# DM1095_LEFT_OV7251.net
KiCad netlist of a schematic drawn in Altium Designer
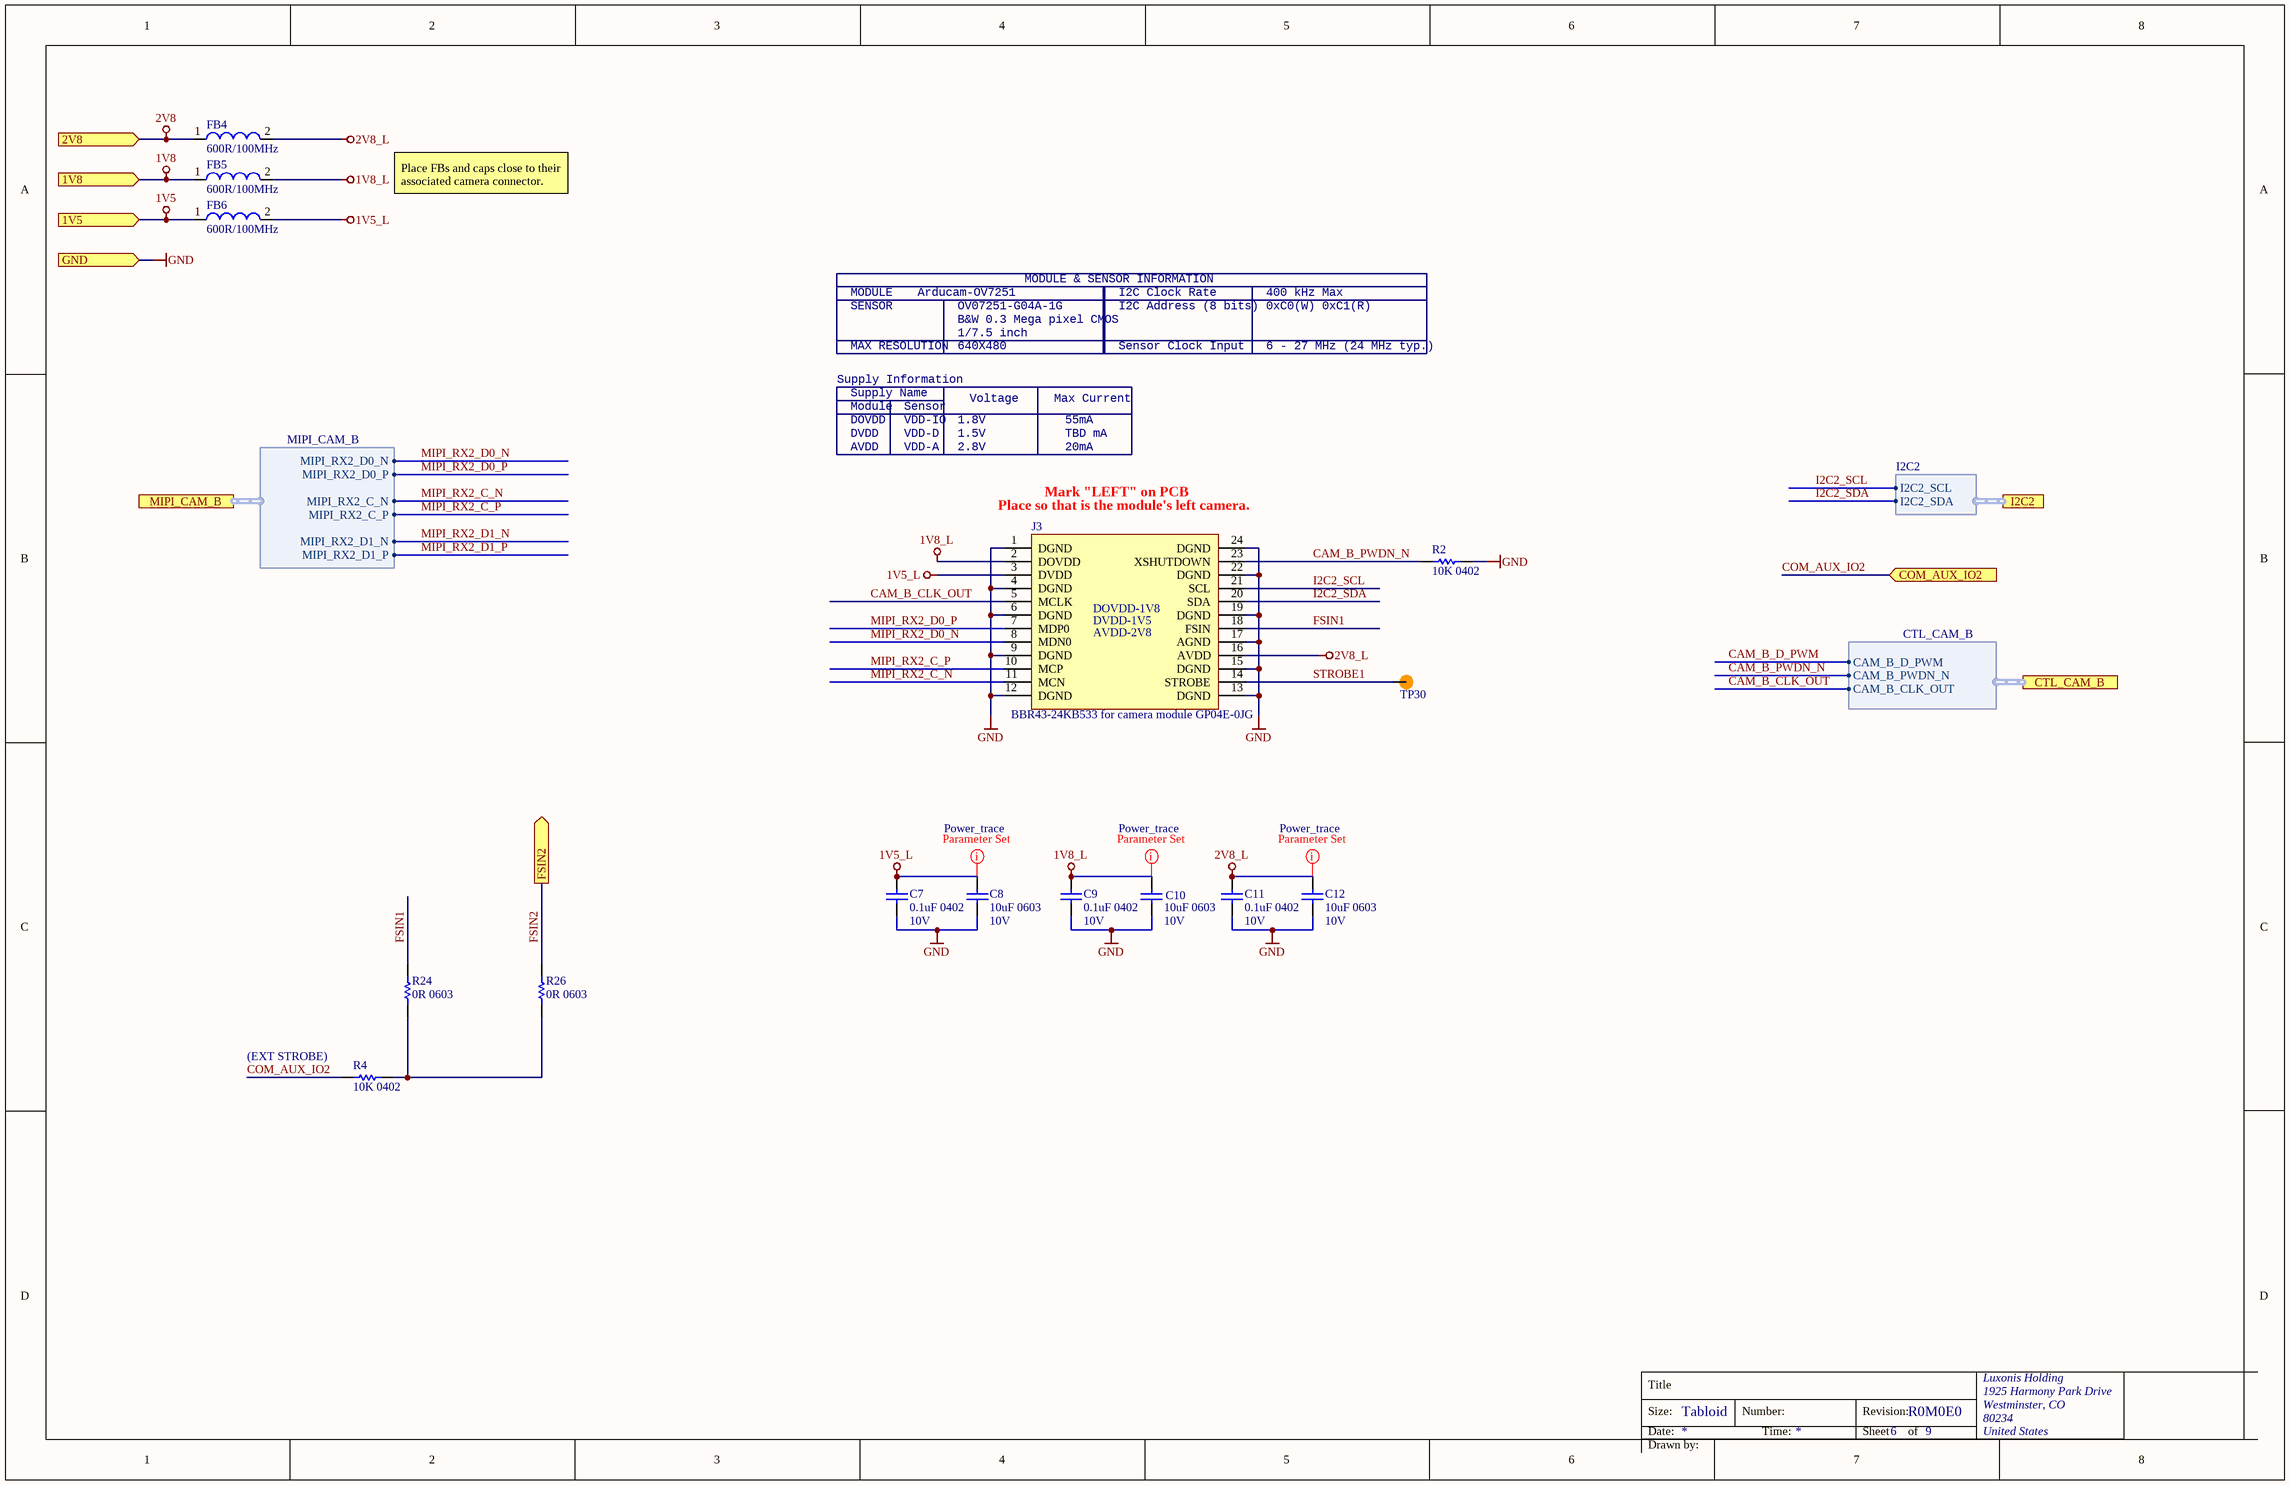
[diagram p0: DM1095_LEFT_OV7251.SchDoc]

(export (version "E")
  (design (tool "Eeschema 10.0.6"))
  (components
    (comp (ref "C7")
      (value "0.1uF 0402")
      (footprint "CAP_Altium_Vault_Generic:CAPC0402(1005)70_L")
      (description "CAP CER 0.1UF 10V X7R 0402 5%")
      (fields (field (name "TOLERANCE") "5%") (field (name "VOLTAGE RATING") "10V"))
      (libsource (lib "LuxonisMaster") (part "GRM155R71A104JA01D"))
    )
    (comp (ref "C8")
      (value "10uF 0603")
      (footprint "CAP_Altium_Vault_Generic:CAPC0603(1608)100_L")
      (description "CAP CER 10UF 10V X5R 0603 20%")
      (fields (field (name "TOLERANCE") "20%") (field (name "VOLTAGE RATING") "10V"))
      (libsource (lib "LuxonisMaster") (part "GRM188R61A106ME69D"))
    )
    (comp (ref "C9")
      (value "0.1uF 0402")
      (footprint "CAP_Altium_Vault_Generic:CAPC0402(1005)70_L")
      (description "CAP CER 0.1UF 10V X7R 0402 5%")
      (fields (field (name "TOLERANCE") "5%") (field (name "VOLTAGE RATING") "10V"))
      (libsource (lib "LuxonisMaster") (part "GRM155R71A104JA01D"))
    )
    (comp (ref "C10")
      (value "10uF 0603")
      (footprint "CAP_Altium_Vault_Generic:CAPC0603(1608)100_L")
      (description "CAP CER 10UF 10V X5R 0603 20%")
      (fields (field (name "TOLERANCE") "20%") (field (name "VOLTAGE RATING") "10V"))
      (libsource (lib "LuxonisMaster") (part "GRM188R61A106ME69D"))
    )
    (comp (ref "C11")
      (value "0.1uF 0402")
      (footprint "CAP_Altium_Vault_Generic:CAPC0402(1005)70_L")
      (description "CAP CER 0.1UF 10V X7R 0402 5%")
      (fields (field (name "TOLERANCE") "5%") (field (name "VOLTAGE RATING") "10V"))
      (libsource (lib "LuxonisMaster") (part "GRM155R71A104JA01D"))
    )
    (comp (ref "C12")
      (value "10uF 0603")
      (footprint "CAP_Altium_Vault_Generic:CAPC0603(1608)100_L")
      (description "CAP CER 10UF 10V X5R 0603 20%")
      (fields (field (name "TOLERANCE") "20%") (field (name "VOLTAGE RATING") "10V"))
      (libsource (lib "LuxonisMaster") (part "GRM188R61A106ME69D"))
    )
    (comp (ref "FB4")
      (value "600R/100MHz")
      (footprint "LuxonisMaster:2508056017Y2")
      (description "FERRITE BEAD, 0.1OHM, 2A, 0805, 600R/100MHz")
      (fields (field (name "TOLERANCE") "25%"))
      (libsource (lib "LuxonisMaster") (part "2508056017Y2"))
    )
    (comp (ref "FB5")
      (value "600R/100MHz")
      (footprint "LuxonisMaster:2508056017Y2")
      (description "FERRITE BEAD, 0.1OHM, 2A, 0805, 600R/100MHz")
      (fields (field (name "TOLERANCE") "25%"))
      (libsource (lib "LuxonisMaster") (part "2508056017Y2"))
    )
    (comp (ref "FB6")
      (value "600R/100MHz")
      (footprint "LuxonisMaster:2508056017Y2")
      (description "FERRITE BEAD, 0.1OHM, 2A, 0805, 600R/100MHz")
      (fields (field (name "TOLERANCE") "25%"))
      (libsource (lib "LuxonisMaster") (part "2508056017Y2"))
    )
    (comp (ref "J3")
      (value "BBR43-24KB533 for camera module GP04E-0JG")
      (footprint "GP04E-0JG OV7251")
      (description "CONN 24 way, 2 row board to board connector SMD")
      (libsource (lib "DM1095") (part "GP04E-0JG_Connector"))
    )
    (comp (ref "R2")
      (value "10K 0402")
      (footprint "RES_Altium_Vault_Generic:RESC0402(1005)_L")
      (fields (field (name "TOLERANCE") "1%"))
      (libsource (lib "LuxonisMaster") (part "RC0402FR-1310KL"))
    )
    (comp (ref "R4")
      (value "10K 0402")
      (footprint "RES_Altium_Vault_Generic:RESC0402(1005)_L")
      (fields (field (name "TOLERANCE") "1%"))
      (libsource (lib "LuxonisMaster") (part "RC0402FR-1310KL"))
    )
    (comp (ref "R24")
      (value "0R 0603")
      (footprint "RES_Altium_Vault_Generic:RESC0603(1608)_N")
      (fields (field (name "TOLERANCE") "5%"))
      (libsource (lib "LuxonisMaster") (part "CRCW06030000Z0EA"))
    )
    (comp (ref "R26")
      (value "0R 0603")
      (footprint "RES_Altium_Vault_Generic:RESC0603(1608)_N")
      (fields (field (name "TOLERANCE") "5%"))
      (libsource (lib "LuxonisMaster") (part "CRCW06030000Z0EA"))
    )
    (comp (ref "TP30")
      (value "TP100_200_NS")
      (footprint "LuxonisMaster:TP100_200_NS")
      (libsource (lib "LuxonisMaster") (part "TEST_POINT"))
    )
  )
  (nets
    (net (code "4") (name "/CAM_B_CLK_OUT") (class "Default")
      (node (ref "J3") (pin "5") (pinfunction "MCLK_5") (pintype "passive"))
    )
    (net (code "6") (name "/CAM_B_PWDN_N") (class "Default")
      (node (ref "J3") (pin "23") (pinfunction "XSHUTDOWN_23") (pintype "passive"))
      (node (ref "R2") (pin "1") (pinfunction "1_1") (pintype "passive"))
    )
    (net (code "7") (name "/COM_AUX_IO2") (class "Default")
      (node (ref "R4") (pin "1") (pinfunction "1_1") (pintype "passive"))
    )
    (net (code "8") (name "/FSIN1") (class "Default")
      (node (ref "J3") (pin "18") (pinfunction "FSIN_18") (pintype "passive"))
      (node (ref "R24") (pin "2") (pinfunction "2_2") (pintype "passive"))
    )
    (net (code "9") (name "/FSIN2") (class "Default")
      (node (ref "R26") (pin "2") (pinfunction "2_2") (pintype "passive"))
    )
    (net (code "10") (name "/I2C2_SCL") (class "Default")
      (node (ref "J3") (pin "21") (pinfunction "SCL_21") (pintype "passive"))
    )
    (net (code "11") (name "/I2C2_SDA") (class "Default")
      (node (ref "J3") (pin "20") (pinfunction "SDA_20") (pintype "passive"))
    )
    (net (code "12") (name "/MIPI_RX2_C_N") (class "Default")
      (node (ref "J3") (pin "11") (pinfunction "MCN_11") (pintype "passive"))
    )
    (net (code "13") (name "/MIPI_RX2_C_P") (class "Default")
      (node (ref "J3") (pin "10") (pinfunction "MCP_10") (pintype "passive"))
    )
    (net (code "14") (name "/MIPI_RX2_D0_N") (class "Default")
      (node (ref "J3") (pin "8") (pinfunction "MDN0_8") (pintype "passive"))
    )
    (net (code "15") (name "/MIPI_RX2_D0_P") (class "Default")
      (node (ref "J3") (pin "7") (pinfunction "MDP0_7") (pintype "passive"))
    )
    (net (code "18") (name "/STROBE1") (class "Default")
      (node (ref "J3") (pin "14") (pinfunction "STROBE_14") (pintype "passive"))
      (node (ref "TP30") (pin "1") (pintype "passive"))
    )
    (net (code "22") (name "1V5") (class "Default")
      (node (ref "FB6") (pin "1") (pinfunction "1_1") (pintype "passive"))
    )
    (net (code "23") (name "1V5_L") (class "Default")
      (node (ref "C7") (pin "2") (pinfunction "2_2") (pintype "passive"))
      (node (ref "C8") (pin "2") (pinfunction "2_2") (pintype "passive"))
      (node (ref "FB6") (pin "2") (pinfunction "2_2") (pintype "passive"))
      (node (ref "J3") (pin "3") (pinfunction "DVDD_3") (pintype "passive"))
    )
    (net (code "24") (name "1V8") (class "Default")
      (node (ref "FB5") (pin "1") (pinfunction "1_1") (pintype "passive"))
    )
    (net (code "25") (name "1V8_L") (class "Default")
      (node (ref "C10") (pin "2") (pinfunction "2_2") (pintype "passive"))
      (node (ref "C9") (pin "2") (pinfunction "2_2") (pintype "passive"))
      (node (ref "FB5") (pin "2") (pinfunction "2_2") (pintype "passive"))
      (node (ref "J3") (pin "2") (pinfunction "DOVDD_2") (pintype "passive"))
    )
    (net (code "26") (name "2V8") (class "Default")
      (node (ref "FB4") (pin "1") (pinfunction "1_1") (pintype "passive"))
    )
    (net (code "27") (name "2V8_L") (class "Default")
      (node (ref "C11") (pin "2") (pinfunction "2_2") (pintype "passive"))
      (node (ref "C12") (pin "2") (pinfunction "2_2") (pintype "passive"))
      (node (ref "FB4") (pin "2") (pinfunction "2_2") (pintype "passive"))
      (node (ref "J3") (pin "16") (pinfunction "AVDD_16") (pintype "passive"))
    )
    (net (code "28") (name "GND") (class "Default")
      (node (ref "C10") (pin "1") (pinfunction "1_1") (pintype "passive"))
      (node (ref "C11") (pin "1") (pinfunction "1_1") (pintype "passive"))
      (node (ref "C12") (pin "1") (pinfunction "1_1") (pintype "passive"))
      (node (ref "C7") (pin "1") (pinfunction "1_1") (pintype "passive"))
      (node (ref "C8") (pin "1") (pinfunction "1_1") (pintype "passive"))
      (node (ref "C9") (pin "1") (pinfunction "1_1") (pintype "passive"))
      (node (ref "J3") (pin "1") (pinfunction "DGND_1") (pintype "passive"))
      (node (ref "J3") (pin "12") (pinfunction "DGND_12") (pintype "passive"))
      (node (ref "J3") (pin "13") (pinfunction "DGND_13") (pintype "passive"))
      (node (ref "J3") (pin "15") (pinfunction "DGND_15") (pintype "passive"))
      (node (ref "J3") (pin "17") (pinfunction "AGND_17") (pintype "passive"))
      (node (ref "J3") (pin "19") (pinfunction "DGND_19") (pintype "passive"))
      (node (ref "J3") (pin "22") (pinfunction "DGND_22") (pintype "passive"))
      (node (ref "J3") (pin "24") (pinfunction "DGND_24") (pintype "passive"))
      (node (ref "J3") (pin "4") (pinfunction "DGND_4") (pintype "passive"))
      (node (ref "J3") (pin "6") (pinfunction "DGND_6") (pintype "passive"))
      (node (ref "J3") (pin "9") (pinfunction "DGND_9") (pintype "passive"))
      (node (ref "R2") (pin "2") (pinfunction "2_2") (pintype "passive"))
    )
    (net (code "29") (name "Net-(R24-Pad1)") (class "Default")
      (node (ref "R24") (pin "1") (pinfunction "1_1") (pintype "passive"))
      (node (ref "R26") (pin "1") (pinfunction "1_1") (pintype "passive"))
      (node (ref "R4") (pin "2") (pinfunction "2_2") (pintype "passive"))
    )
  )
)
